# openmv4.net
KiCad netlist of a schematic drawn in Altium Designer
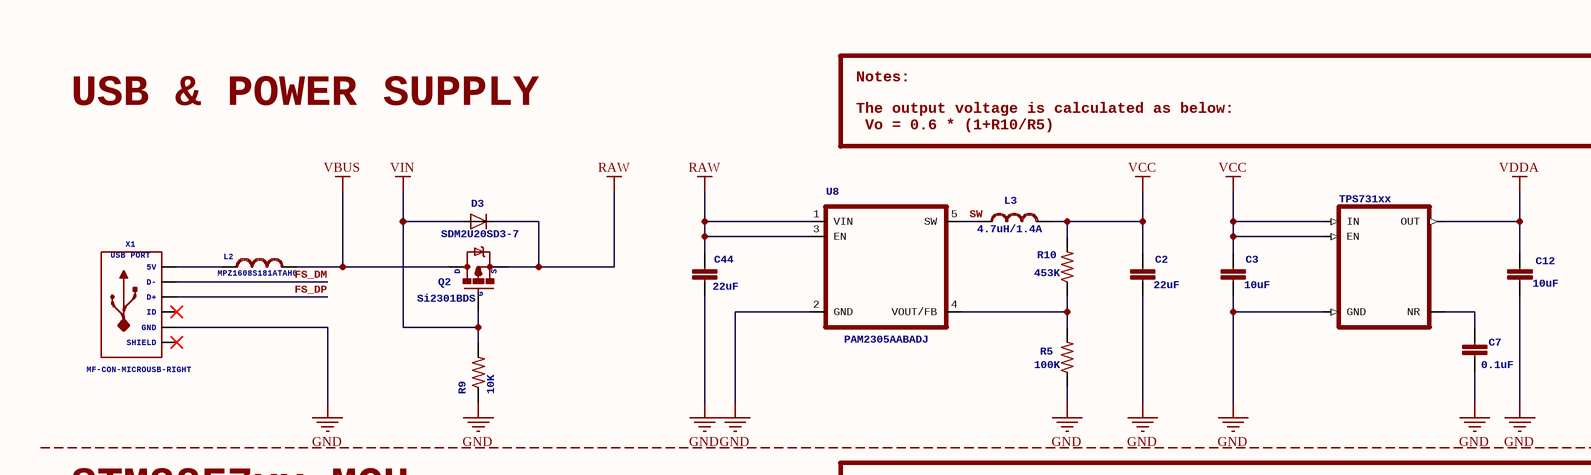
[diagram p0: openmv4.SchDoc, top left]
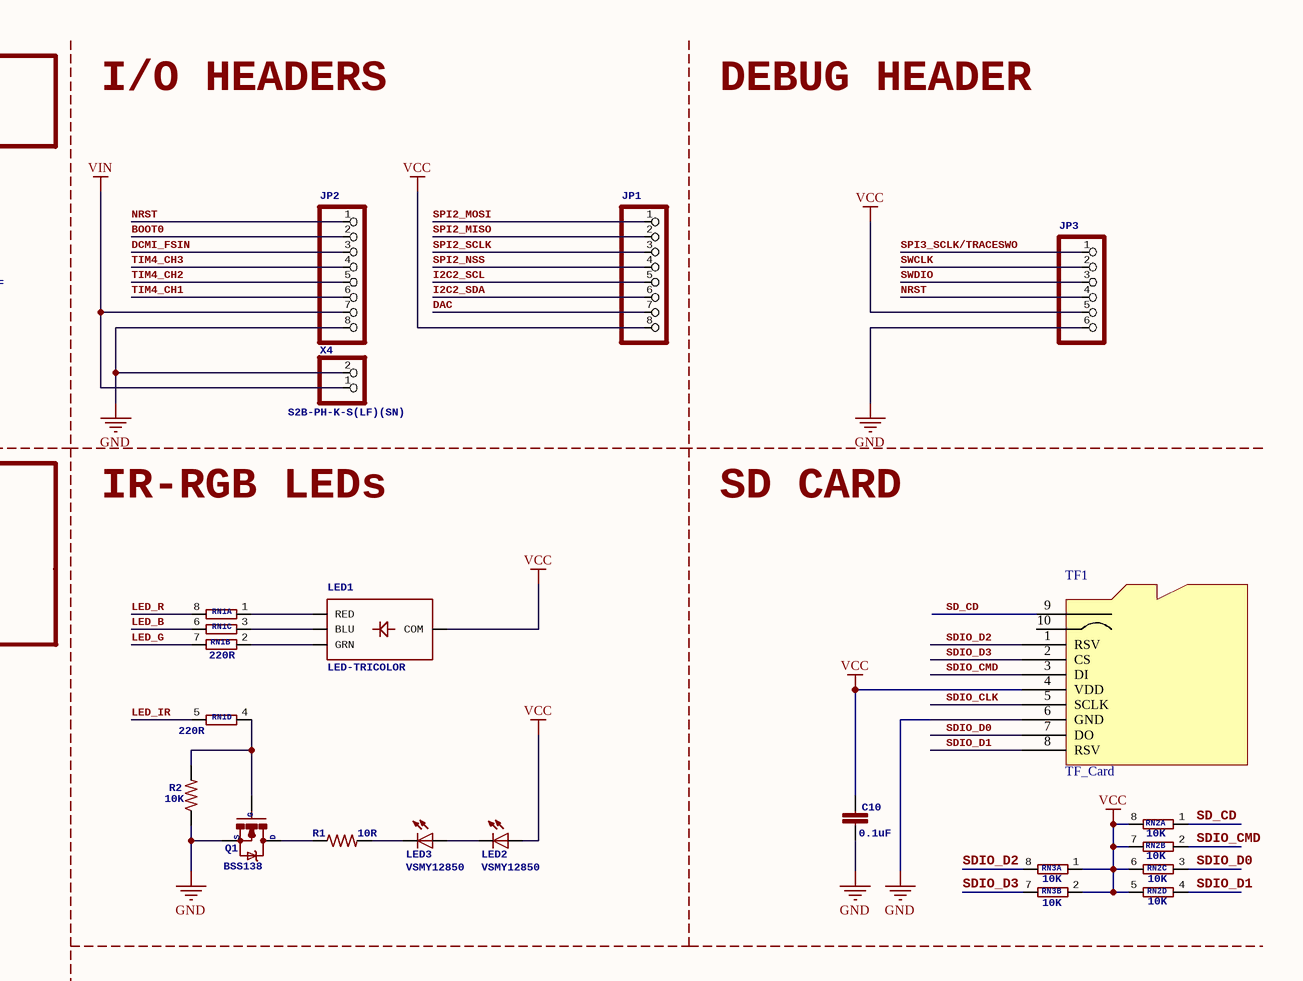
[diagram p1: openmv4.SchDoc, top right]
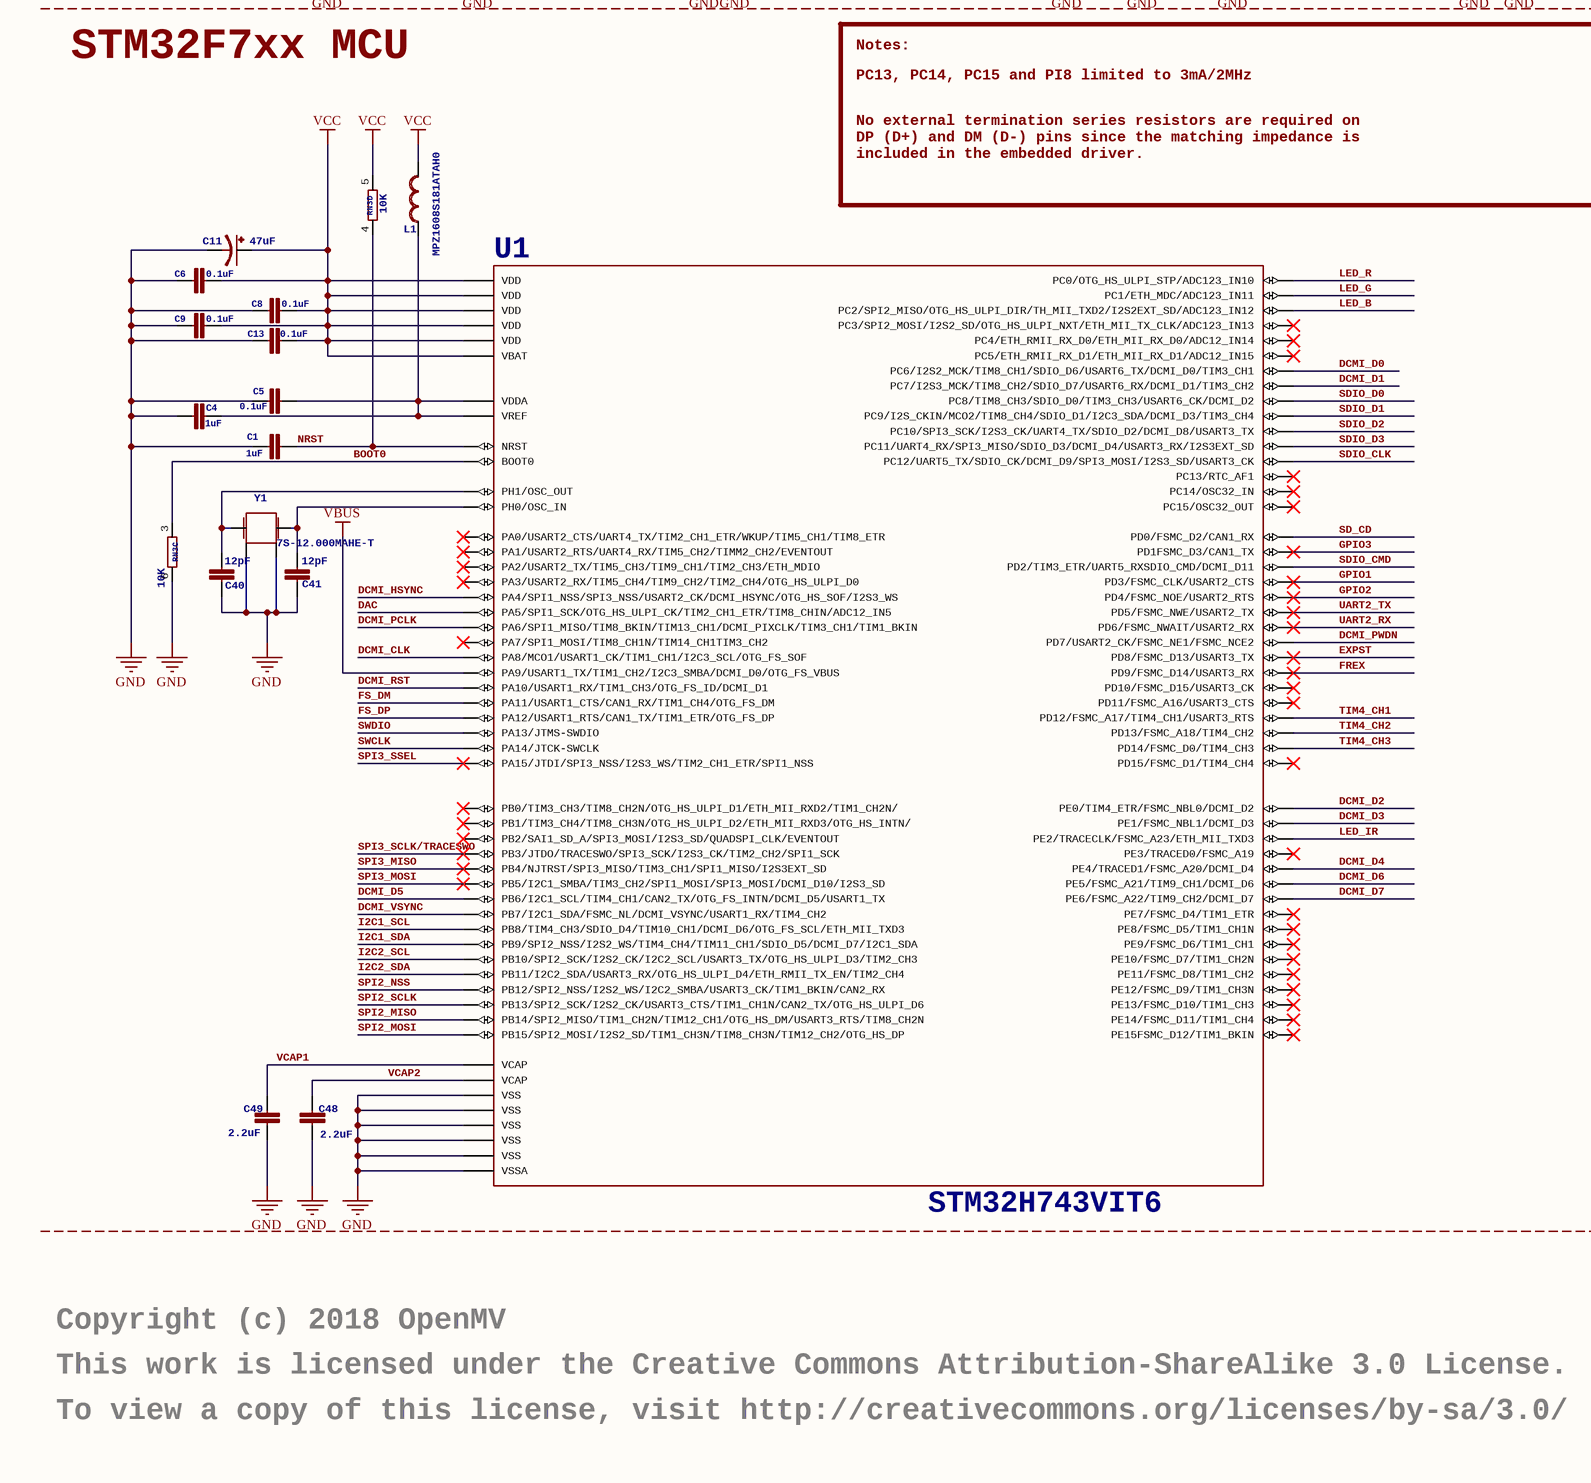
[diagram p2: openmv4.SchDoc, bottom left]
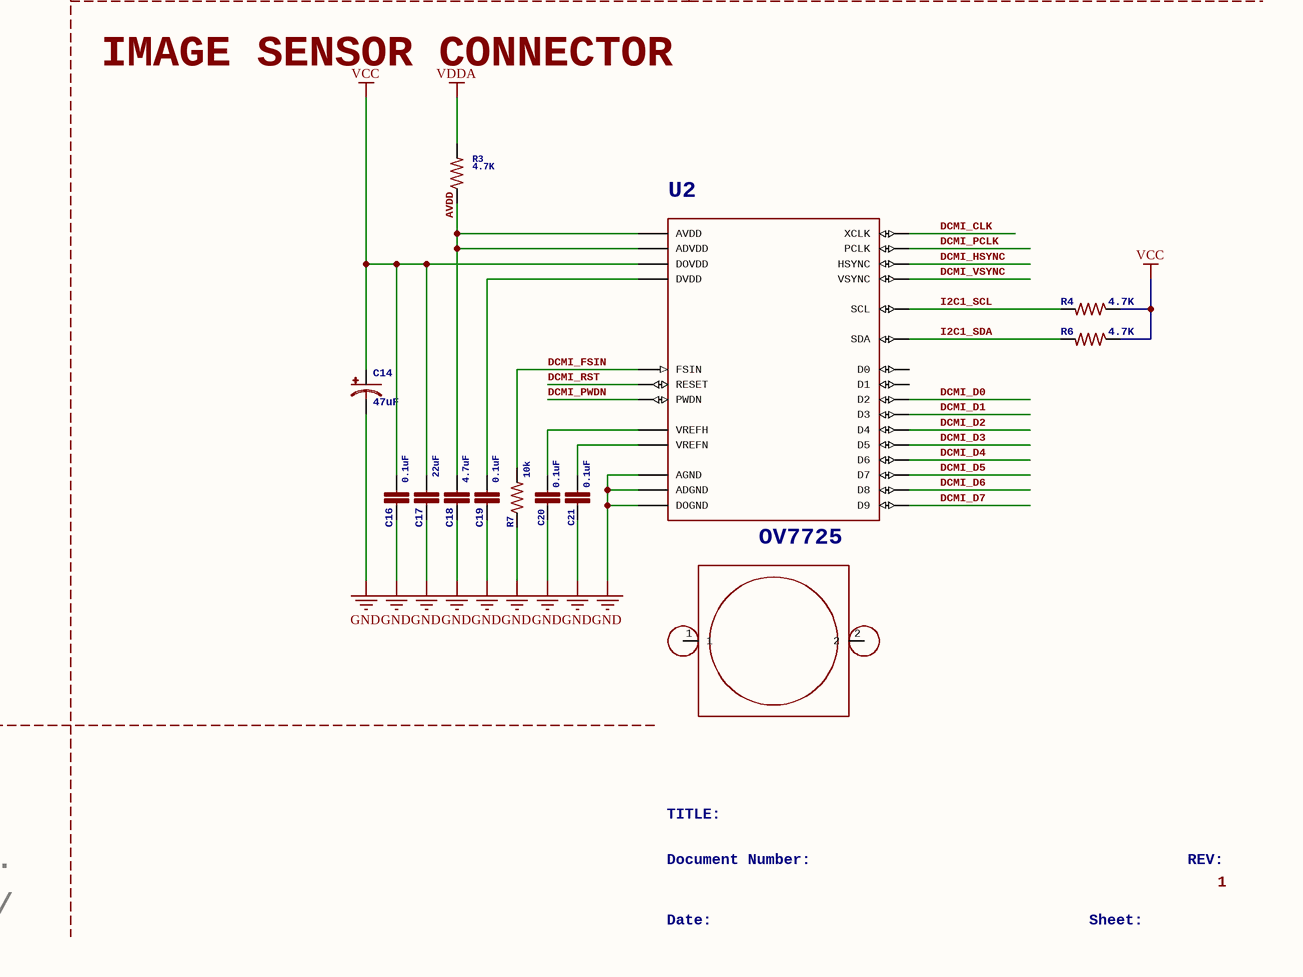
[diagram p3: openmv4.SchDoc, bottom right]

(export (version "E")
  (design (tool "Eeschema 10.0.6"))
  (components
    (comp (ref "C1")
      (value "1uF")
      (footprint "C0603")
      (description "CapacitorStandard 0603 ceramic capacitor, and 0.1\" leaded capacitor.")
      (libsource (lib "sfe") (part "CAP0603-CAP"))
    )
    (comp (ref "C2")
      (value "22uF")
      (footprint "C0805")
      (description "CapacitorStandard 0603 ceramic capacitor, and 0.1\" leaded capacitor.")
      (libsource (lib "") (part "CAP0805_1"))
    )
    (comp (ref "C3")
      (value "10uF")
      (footprint "C0805")
      (description "CapacitorStandard 0603 ceramic capacitor, and 0.1\" leaded capacitor.")
      (libsource (lib "") (part "CAP0805_1"))
    )
    (comp (ref "C4")
      (value "1uF")
      (footprint "C0603")
      (description "CapacitorStandard 0603 ceramic capacitor, and 0.1\" leaded capacitor.")
      (libsource (lib "sfe") (part "CAP0603-CAP"))
    )
    (comp (ref "C5")
      (value "0.1uF")
      (footprint "C0603")
      (description "CapacitorStandard 0603 ceramic capacitor, and 0.1\" leaded capacitor.")
      (libsource (lib "sfe") (part "CAP0603-CAP"))
    )
    (comp (ref "C6")
      (value "0.1uF")
      (footprint "C0603")
      (description "CapacitorStandard 0603 ceramic capacitor, and 0.1\" leaded capacitor.")
      (libsource (lib "sfe") (part "CAP0603-CAP"))
    )
    (comp (ref "C7")
      (value "0.1uF")
      (footprint "C0603")
      (description "CapacitorStandard 0603 ceramic capacitor, and 0.1\" leaded capacitor.")
      (libsource (lib "") (part "CAP0603-CAP_1"))
    )
    (comp (ref "C8")
      (value "0.1uF")
      (footprint "C0603")
      (description "CapacitorStandard 0603 ceramic capacitor, and 0.1\" leaded capacitor.")
      (libsource (lib "sfe") (part "CAP0603-CAP"))
    )
    (comp (ref "C9")
      (value "0.1uF")
      (footprint "C0603")
      (description "CapacitorStandard 0603 ceramic capacitor, and 0.1\" leaded capacitor.")
      (libsource (lib "sfe") (part "CAP0603-CAP"))
    )
    (comp (ref "C10")
      (value "0.1uF")
      (footprint "C0603")
      (description "CapacitorStandard 0603 ceramic capacitor, and 0.1\" leaded capacitor.")
      (libsource (lib "") (part "CAP0603-CAP_1"))
    )
    (comp (ref "C11") (value "47uF") (footprint "EIA3216") (libsource (lib "sfe") (part "CAP_POL1206")))
    (comp (ref "C12")
      (value "10uF")
      (footprint "C0805")
      (description "CapacitorStandard 0603 ceramic capacitor, and 0.1\" leaded capacitor.")
      (libsource (lib "") (part "CAP0805_1"))
    )
    (comp (ref "C13")
      (value "0.1uF")
      (footprint "C0603")
      (description "CapacitorStandard 0603 ceramic capacitor, and 0.1\" leaded capacitor.")
      (libsource (lib "sfe") (part "CAP0603-CAP"))
    )
    (comp (ref "C14") (value "47uF") (footprint "EIA3216") (libsource (lib "") (part "CAP_POL1206_1")))
    (comp (ref "C16")
      (value "0.1uF")
      (footprint "C0603")
      (description "CapacitorStandard 0603 ceramic capacitor, and 0.1\" leaded capacitor.")
      (libsource (lib "sfe") (part "CAP0603-CAP"))
    )
    (comp (ref "C17")
      (value "22uF")
      (footprint "C0805")
      (description "CapacitorStandard 0603 ceramic capacitor, and 0.1\" leaded capacitor.")
      (libsource (lib "sfe") (part "CAP0805"))
    )
    (comp (ref "C18")
      (value "4.7uF")
      (footprint "C0603")
      (description "CapacitorStandard 0603 ceramic capacitor, and 0.1\" leaded capacitor.")
      (libsource (lib "sfe") (part "CAP0603-CAP"))
    )
    (comp (ref "C19")
      (value "0.1uF")
      (footprint "C0603")
      (description "CapacitorStandard 0603 ceramic capacitor, and 0.1\" leaded capacitor.")
      (libsource (lib "sfe") (part "CAP0603-CAP"))
    )
    (comp (ref "C20")
      (value "0.1uF")
      (footprint "C0603")
      (description "CapacitorStandard 0603 ceramic capacitor, and 0.1\" leaded capacitor.")
      (libsource (lib "") (part "CAP0603-CAP_1"))
    )
    (comp (ref "C21")
      (value "0.1uF")
      (footprint "C0603")
      (description "CapacitorStandard 0603 ceramic capacitor, and 0.1\" leaded capacitor.")
      (libsource (lib "") (part "CAP0603-CAP_1"))
    )
    (comp (ref "C40")
      (value "12pF")
      (footprint "C0603")
      (description "CapacitorStandard 0603 ceramic capacitor, and 0.1\" leaded capacitor.")
      (libsource (lib "") (part "CAP0603-CAP_2"))
    )
    (comp (ref "C41")
      (value "12pF")
      (footprint "C0603")
      (description "CapacitorStandard 0603 ceramic capacitor, and 0.1\" leaded capacitor.")
      (libsource (lib "") (part "CAP0603-CAP_2"))
    )
    (comp (ref "C44")
      (value "22uF")
      (footprint "C0805")
      (description "CapacitorStandard 0603 ceramic capacitor, and 0.1\" leaded capacitor.")
      (libsource (lib "") (part "CAP0805_1"))
    )
    (comp (ref "C48")
      (value "2.2uF")
      (footprint "C0603")
      (description "CapacitorStandard 0603 ceramic capacitor, and 0.1\" leaded capacitor.")
      (libsource (lib "") (part "CAP0603-CAP_1"))
    )
    (comp (ref "C49")
      (value "2.2uF")
      (footprint "C0603")
      (description "CapacitorStandard 0603 ceramic capacitor, and 0.1\" leaded capacitor.")
      (libsource (lib "") (part "CAP0603-CAP_1"))
    )
    (comp (ref "D3") (value "SDM2U20SD3-7") (footprint "SOD323") (libsource (lib "sfe") (part "DIODESOD")))
    (comp (ref "JP1")
      (value "PINHD-1X8")
      (footprint "1X08")
      (description "PIN HEADER")
      (libsource (lib "pinhead") (part "PINHD-1X8"))
    )
    (comp (ref "JP2")
      (value "PINHD-1X8")
      (footprint "1X08")
      (description "PIN HEADER")
      (libsource (lib "pinhead") (part "PINHD-1X8"))
    )
    (comp (ref "JP3")
      (value "PINHD-1X6")
      (footprint "1X06")
      (description "PIN HEADER")
      (libsource (lib "pinhead") (part "PINHD-1X6"))
    )
    (comp (ref "L1")
      (value "MPZ1608S181ATAH0")
      (footprint "l0603")
      (libsource (lib "sfe") (part "INDUCTOR0603"))
    )
    (comp (ref "L2")
      (value "MPZ1608S181ATAH0")
      (footprint "l0603")
      (libsource (lib "sfe") (part "INDUCTOR0603"))
    )
    (comp (ref "L3") (value "4.7uH/1.4A") (footprint "1007") (libsource (lib "sfe") (part "INDUCTOR1007")))
    (comp (ref "LED1")
      (value "LED-TRICOLOR")
      (footprint "LED-TRICOLOR-SMD-MF")
      (libsource (lib "sfe") (part "LED-TRICOLOR"))
    )
    (comp (ref "LED2") (value "VSMY12850") (footprint "LED-1206") (libsource (lib "sfe") (part "LED1206")))
    (comp (ref "LED3") (value "VSMY12850") (footprint "LED-1206") (libsource (lib "sfe") (part "LED1206")))
    (comp (ref "LM1")
      (value "LENSMOUNT20MM")
      (footprint "LENSMOUNT-20MM")
      (libsource (lib "omnivision") (part "LENSMOUNT20MM"))
    )
    (comp (ref "Q1")
      (value "BSS138")
      (footprint "SOT23-3")
      (fields (field (name "D") "D") (field (name "S") "S") (field (name "G") "G"))
      (libsource (lib "sfe") (part "MOSFET-NCHANNELSMD"))
    )
    (comp (ref "Q2")
      (value "Si2301BDS")
      (footprint "SOT23-3")
      (fields (field (name "D") "D") (field (name "S") "S") (field (name "G") "G"))
      (libsource (lib "sfe") (part "MOSFET-PCHANNELSMD"))
    )
    (comp (ref "R1")
      (value "10R")
      (footprint "R0603")
      (description "ResistorBasic schematic elements and footprints for 0603, 1206, and PTH resistors.")
      (libsource (lib "sfe") (part "RESISTOR0603-RES"))
    )
    (comp (ref "R2")
      (value "10K")
      (footprint "R0603")
      (description "ResistorBasic schematic elements and footprints for 0603, 1206, and PTH resistors.")
      (libsource (lib "sfe") (part "RESISTOR0603-RES"))
    )
    (comp (ref "R3")
      (value "4.7K")
      (footprint "R0603")
      (description "ResistorBasic schematic elements and footprints for 0603, 1206, and PTH resistors.")
      (libsource (lib "sfe") (part "RESISTOR0603-RES"))
    )
    (comp (ref "R4")
      (value "4.7K")
      (footprint "R0603")
      (description "ResistorBasic schematic elements and footprints for 0603, 1206, and PTH resistors.")
      (libsource (lib "sfe") (part "RESISTOR0603-RES"))
    )
    (comp (ref "R5")
      (value "100K")
      (footprint "R0603")
      (description "ResistorBasic schematic elements and footprints for 0603, 1206, and PTH resistors.")
      (libsource (lib "sfe") (part "RESISTOR0603-RES"))
    )
    (comp (ref "R6")
      (value "4.7K")
      (footprint "R0603")
      (description "ResistorBasic schematic elements and footprints for 0603, 1206, and PTH resistors.")
      (libsource (lib "sfe") (part "RESISTOR0603-RES"))
    )
    (comp (ref "R7")
      (value "10k")
      (footprint "R0603")
      (description "ResistorBasic schematic elements and footprints for 0603, 1206, and PTH resistors.")
      (libsource (lib "sfe") (part "RESISTOR0603-RES"))
    )
    (comp (ref "R9")
      (value "10K")
      (footprint "R0603")
      (description "ResistorBasic schematic elements and footprints for 0603, 1206, and PTH resistors.")
      (libsource (lib "sfe") (part "RESISTOR0603-RES"))
    )
    (comp (ref "R10")
      (value "453K")
      (footprint "R0603")
      (description "ResistorBasic schematic elements and footprints for 0603, 1206, and PTH resistors.")
      (libsource (lib "sfe") (part "RESISTOR0603-RES"))
    )
    (comp (ref "RN1")
      (value "220R")
      (footprint "EXBV8V")
      (description "Array Chip Resistor   Source: RS Component / Phycomp")
      (libsource (lib "resistor-dil") (part "4R-NEXBV8V"))
    )
    (comp (ref "RN2")
      (value "10K")
      (footprint "EXBV8V")
      (description "Array Chip Resistor   Source: RS Component / Phycomp")
      (libsource (lib "resistor-dil") (part "4R-NEXBV8V"))
    )
    (comp (ref "RN3")
      (value "10K")
      (footprint "EXBV8V")
      (description "Array Chip Resistor   Source: RS Component / Phycomp")
      (libsource (lib "resistor-dil") (part "4R-NEXBV8V"))
    )
    (comp (ref "TF1")
      (value "TF_Card")
      (footprint "TF-2")
      (libsource (lib "Desiger_Schlib") (part "TF_CADE"))
    )
    (comp (ref "U1")
      (value "STM32H743VIT6")
      (footprint "LQFP100")
      (libsource (lib "stm32") (part "STM32F746LQFP100"))
    )
    (comp (ref "U2") (value "OV7725") (footprint "CSP2-28") (libsource (lib "omnivision") (part "OV7725")))
    (comp (ref "U5")
      (value "TPS731XX")
      (footprint "SOT23-5")
      (fields (field (name "TPS731XX") "TPS731xx"))
      (libsource (lib "mux") (part "TPS731XX"))
    )
    (comp (ref "U8")
      (value "PAM2305AABADJ")
      (footprint "SOT23-5")
      (libsource (lib "regulators") (part "PAM2305AAB330"))
    )
    (comp (ref "X1")
      (value "MF-CON-MICROUSB-RIGHT")
      (footprint "MICROUSB-RIGHT")
      (fields
        (field (name "USBPORT") "USB PORT")
        (field (name "5V") "5V")
        (field (name "D-") "D-")
        (field (name "D+") "D+")
        (field (name "ID") "ID")
        (field (name "GND") "GND")
        (field (name "SHIELD") "SHIELD")
      )
      (libsource (lib "MF_Connectors") (part "USB_MICRO_RIGHT"))
    )
    (comp (ref "X4")
      (value "S2B-PH-K-S(LF)(SN)")
      (footprint "JST-PH-2-THM-RA")
      (libsource (lib "adafruit-updated") (part "JST_2PIN-THM-RA"))
    )
    (comp (ref "Y1")
      (value "7S-12.000MAHE-T")
      (footprint "XTAL-SMD-3225_4P")
      (description "CrystalsVarious standard crystals. Proven footprints. Spark Fun Electronics SKU : COM-00534")
      (libsource (lib "mux") (part "CRYSTAL2.5X2.0"))
    )
  )
  (nets
    (net (code "1") (name "/AVDD") (class "Default")
      (node (ref "C18") (pin "1") (pinfunction "1_1") (pintype "passive"))
      (node (ref "R3") (pin "1") (pinfunction "1_1") (pintype "passive"))
      (node (ref "U2") (pin "A1") (pinfunction "ADVDD_A1") (pintype "power_in"))
      (node (ref "U2") (pin "B3") (pinfunction "AVDD_B3") (pintype "power_in"))
    )
    (net (code "2") (name "/BOOT0") (class "Default")
      (node (ref "JP2") (pin "2") (pinfunction "2_2") (pintype "passive"))
      (node (ref "RN3") (pin "3") (pinfunction "1_3") (pintype "passive"))
      (node (ref "U1") (pin "94") (pinfunction "BOOT0_94") (pintype "bidirectional"))
    )
    (net (code "3") (name "/DAC") (class "Default")
      (node (ref "JP1") (pin "7") (pinfunction "7_7") (pintype "passive"))
      (node (ref "U1") (pin "29") (pinfunction "PA5/SPI1_SCK/OTG_HS_ULPI_CK/TIM2_CH1_ETR/TIM8_CHIN/ADC12_IN5_29") (pintype "bidirectional"))
    )
    (net (code "4") (name "/DCMI_CLK") (class "Default")
      (node (ref "U1") (pin "67") (pinfunction "PA8/MCO1/USART1_CK/TIM1_CH1/I2C3_SCL/OTG_FS_SOF_67") (pintype "bidirectional"))
      (node (ref "U2") (pin "F3") (pinfunction "XCLK_F3") (pintype "bidirectional"))
    )
    (net (code "5") (name "/DCMI_D0") (class "Default")
      (node (ref "U1") (pin "63") (pinfunction "PC6/I2S2_MCK/TIM8_CH1/SDIO_D6/USART6_TX/DCMI_D0/TIM3_CH1_63") (pintype "bidirectional"))
      (node (ref "U2") (pin "F5") (pinfunction "D2_F5") (pintype "bidirectional"))
    )
    (net (code "6") (name "/DCMI_D1") (class "Default")
      (node (ref "U1") (pin "64") (pinfunction "PC7/I2S3_MCK/TIM8_CH2/SDIO_D7/USART6_RX/DCMI_D1/TIM3_CH2_64") (pintype "bidirectional"))
      (node (ref "U2") (pin "F2") (pinfunction "D3_F2") (pintype "bidirectional"))
    )
    (net (code "7") (name "/DCMI_D2") (class "Default")
      (node (ref "U1") (pin "97") (pinfunction "PE0/TIM4_ETR/FSMC_NBL0/DCMI_D2_97") (pintype "bidirectional"))
      (node (ref "U2") (pin "D6") (pinfunction "D4_D6") (pintype "bidirectional"))
    )
    (net (code "8") (name "/DCMI_D3") (class "Default")
      (node (ref "U1") (pin "98") (pinfunction "PE1/FSMC_NBL1/DCMI_D3_98") (pintype "bidirectional"))
      (node (ref "U2") (pin "D1") (pinfunction "D5_D1") (pintype "bidirectional"))
    )
    (net (code "9") (name "/DCMI_D4") (class "Default")
      (node (ref "U1") (pin "3") (pinfunction "PE4/TRACED1/FSMC_A20/DCMI_D4_3") (pintype "bidirectional"))
      (node (ref "U2") (pin "E6") (pinfunction "D6_E6") (pintype "bidirectional"))
    )
    (net (code "10") (name "/DCMI_D5") (class "Default")
      (node (ref "U1") (pin "92") (pinfunction "PB6/I2C1_SCL/TIM4_CH1/CAN2_TX/OTG_FS_INTN/DCMI_D5/USART1_TX_92") (pintype "bidirectional"))
      (node (ref "U2") (pin "E1") (pinfunction "D7_E1") (pintype "bidirectional"))
    )
    (net (code "11") (name "/DCMI_D6") (class "Default")
      (node (ref "U1") (pin "4") (pinfunction "PE5/FSMC_A21/TIM9_CH1/DCMI_D6_4") (pintype "bidirectional"))
      (node (ref "U2") (pin "F6") (pinfunction "D8_F6") (pintype "bidirectional"))
    )
    (net (code "12") (name "/DCMI_D7") (class "Default")
      (node (ref "U1") (pin "5") (pinfunction "PE6/FSMC_A22/TIM9_CH2/DCMI_D7_5") (pintype "bidirectional"))
      (node (ref "U2") (pin "F1") (pinfunction "D9_F1") (pintype "bidirectional"))
    )
    (net (code "13") (name "/DCMI_FSIN") (class "Default")
      (node (ref "JP2") (pin "3") (pinfunction "3_3") (pintype "passive"))
      (node (ref "R7") (pin "2") (pinfunction "2_2") (pintype "passive"))
      (node (ref "U2") (pin "A4") (pinfunction "FSIN_A4") (pintype "input"))
    )
    (net (code "14") (name "/DCMI_HSYNC") (class "Default")
      (node (ref "U1") (pin "28") (pinfunction "PA4/SPI1_NSS/SPI3_NSS/USART2_CK/DCMI_HSYNC/OTG_HS_SOF/I2S3_WS_28") (pintype "bidirectional"))
      (node (ref "U2") (pin "B6") (pinfunction "HSYNC_B6") (pintype "bidirectional"))
    )
    (net (code "15") (name "/DCMI_PCLK") (class "Default")
      (node (ref "U1") (pin "30") (pinfunction "PA6/SPI1_MISO/TIM8_BKIN/TIM13_CH1/DCMI_PIXCLK/TIM3_CH1/TIM1_BKIN_30") (pintype "bidirectional"))
      (node (ref "U2") (pin "E4") (pinfunction "PCLK_E4") (pintype "bidirectional"))
    )
    (net (code "16") (name "/DCMI_PWDN") (class "Default")
      (node (ref "U1") (pin "88") (pinfunction "PD7/USART2_CK/FSMC_NE1/FSMC_NCE2_88") (pintype "bidirectional"))
      (node (ref "U2") (pin "C1") (pinfunction "PWDN_C1") (pintype "bidirectional"))
    )
    (net (code "17") (name "/DCMI_RST") (class "Default")
      (node (ref "U1") (pin "69") (pinfunction "PA10/USART1_RX/TIM1_CH3/OTG_FS_ID/DCMI_D1_69") (pintype "bidirectional"))
      (node (ref "U2") (pin "A2") (pinfunction "RESET_A2") (pintype "bidirectional"))
    )
    (net (code "18") (name "/DCMI_VSYNC") (class "Default")
      (node (ref "U1") (pin "93") (pinfunction "PB7/I2C1_SDA/FSMC_NL/DCMI_VSYNC/USART1_RX/TIM4_CH2_93") (pintype "bidirectional"))
      (node (ref "U2") (pin "C6") (pinfunction "VSYNC_C6") (pintype "bidirectional"))
    )
    (net (code "19") (name "/EXPST") (class "Default")
      (node (ref "U1") (pin "55") (pinfunction "PD8/FSMC_D13/USART3_TX_55") (pintype "bidirectional+no_connect"))
    )
    (net (code "20") (name "/FREX") (class "Default")
      (node (ref "U1") (pin "56") (pinfunction "PD9/FSMC_D14/USART3_RX_56") (pintype "bidirectional+no_connect"))
    )
    (net (code "21") (name "/FS_DM") (class "Default")
      (node (ref "U1") (pin "70") (pinfunction "PA11/USART1_CTS/CAN1_RX/TIM1_CH4/OTG_FS_DM_70") (pintype "bidirectional"))
      (node (ref "X1") (pin "2") (pinfunction "D-_2") (pintype "bidirectional"))
    )
    (net (code "22") (name "/FS_DP") (class "Default")
      (node (ref "U1") (pin "71") (pinfunction "PA12/USART1_RTS/CAN1_TX/TIM1_ETR/OTG_FS_DP_71") (pintype "bidirectional"))
      (node (ref "X1") (pin "3") (pinfunction "D+_3") (pintype "bidirectional"))
    )
    (net (code "23") (name "/GPIO1") (class "Default")
      (node (ref "U1") (pin "84") (pinfunction "PD3/FSMC_CLK/USART2_CTS_84") (pintype "bidirectional+no_connect"))
    )
    (net (code "24") (name "/GPIO2") (class "Default")
      (node (ref "U1") (pin "85") (pinfunction "PD4/FSMC_NOE/USART2_RTS_85") (pintype "bidirectional+no_connect"))
    )
    (net (code "25") (name "/GPIO3") (class "Default")
      (node (ref "U1") (pin "82") (pinfunction "PD1FSMC_D3/CAN1_TX_82") (pintype "bidirectional+no_connect"))
    )
    (net (code "26") (name "/I2C1_SCL") (class "Default")
      (node (ref "R4") (pin "2") (pinfunction "2_2") (pintype "passive"))
      (node (ref "U1") (pin "95") (pinfunction "PB8/TIM4_CH3/SDIO_D4/TIM10_CH1/DCMI_D6/OTG_FS_SCL/ETH_MII_TXD3_95") (pintype "bidirectional"))
      (node (ref "U2") (pin "A5") (pinfunction "SCL_A5") (pintype "bidirectional"))
    )
    (net (code "27") (name "/I2C1_SDA") (class "Default")
      (node (ref "R6") (pin "2") (pinfunction "2_2") (pintype "passive"))
      (node (ref "U1") (pin "96") (pinfunction "PB9/SPI2_NSS/I2S2_WS/TIM4_CH4/TIM11_CH1/SDIO_D5/DCMI_D7/I2C1_SDA_96") (pintype "bidirectional"))
      (node (ref "U2") (pin "B5") (pinfunction "SDA_B5") (pintype "bidirectional"))
    )
    (net (code "28") (name "/I2C2_SCL") (class "Default")
      (node (ref "JP1") (pin "5") (pinfunction "5_5") (pintype "passive"))
      (node (ref "U1") (pin "46") (pinfunction "PB10/SPI2_SCK/I2S2_CK/I2C2_SCL/USART3_TX/OTG_HS_ULPI_D3/TIM2_CH3_46") (pintype "bidirectional"))
    )
    (net (code "29") (name "/I2C2_SDA") (class "Default")
      (node (ref "JP1") (pin "6") (pinfunction "6_6") (pintype "passive"))
      (node (ref "U1") (pin "47") (pinfunction "PB11/I2C2_SDA/USART3_RX/OTG_HS_ULPI_D4/ETH_RMII_TX_EN/TIM2_CH4_47") (pintype "bidirectional"))
    )
    (net (code "30") (name "/LED_B") (class "Default")
      (node (ref "RN1") (pin "6") (pinfunction "2_6") (pintype "passive"))
      (node (ref "U1") (pin "17") (pinfunction "PC2/SPI2_MISO/OTG_HS_ULPI_DIR/TH_MII_TXD2/I2S2EXT_SD/ADC123_IN12_17") (pintype "bidirectional"))
    )
    (net (code "31") (name "/LED_G") (class "Default")
      (node (ref "RN1") (pin "7") (pinfunction "2_7") (pintype "passive"))
      (node (ref "U1") (pin "16") (pinfunction "PC1/ETH_MDC/ADC123_IN11_16") (pintype "bidirectional"))
    )
    (net (code "32") (name "/LED_IR") (class "Default")
      (node (ref "RN1") (pin "5") (pinfunction "2_5") (pintype "passive"))
      (node (ref "U1") (pin "1") (pinfunction "PE2/TRACECLK/FSMC_A23/ETH_MII_TXD3_1") (pintype "bidirectional"))
    )
    (net (code "33") (name "/LED_R") (class "Default")
      (node (ref "RN1") (pin "8") (pinfunction "2_8") (pintype "passive"))
      (node (ref "U1") (pin "15") (pinfunction "PC0/OTG_HS_ULPI_STP/ADC123_IN10_15") (pintype "bidirectional"))
    )
    (net (code "34") (name "/NRST") (class "Default")
      (node (ref "C1") (pin "1") (pinfunction "1_1") (pintype "passive"))
      (node (ref "JP2") (pin "1") (pinfunction "1_1") (pintype "passive"))
      (node (ref "JP3") (pin "4") (pinfunction "4_4") (pintype "passive"))
      (node (ref "RN3") (pin "4") (pinfunction "1_4") (pintype "passive"))
      (node (ref "U1") (pin "14") (pinfunction "NRST_14") (pintype "bidirectional"))
    )
    (net (code "35") (name "/SDIO_CLK") (class "Default")
      (node (ref "TF1") (pin "5") (pinfunction "SCLK_5") (pintype "passive"))
      (node (ref "U1") (pin "80") (pinfunction "PC12/UART5_TX/SDIO_CK/DCMI_D9/SPI3_MOSI/I2S3_SD/USART3_CK_80") (pintype "bidirectional"))
    )
    (net (code "36") (name "/SDIO_CMD") (class "Default")
      (node (ref "RN2") (pin "2") (pinfunction "1_2") (pintype "passive"))
      (node (ref "TF1") (pin "3") (pinfunction "DI_3") (pintype "passive"))
      (node (ref "U1") (pin "83") (pinfunction "PD2/TIM3_ETR/UART5_RXSDIO_CMD/DCMI_D11_83") (pintype "bidirectional"))
    )
    (net (code "37") (name "/SDIO_D0") (class "Default")
      (node (ref "RN2") (pin "3") (pinfunction "1_3") (pintype "passive"))
      (node (ref "TF1") (pin "7") (pinfunction "DO_7") (pintype "passive"))
      (node (ref "U1") (pin "65") (pinfunction "PC8/TIM8_CH3/SDIO_D0/TIM3_CH3/USART6_CK/DCMI_D2_65") (pintype "bidirectional"))
    )
    (net (code "38") (name "/SDIO_D1") (class "Default")
      (node (ref "RN2") (pin "4") (pinfunction "1_4") (pintype "passive"))
      (node (ref "TF1") (pin "8") (pinfunction "RSV_8") (pintype "passive"))
      (node (ref "U1") (pin "66") (pinfunction "PC9/I2S_CKIN/MCO2/TIM8_CH4/SDIO_D1/I2C3_SDA/DCMI_D3/TIM3_CH4_66") (pintype "bidirectional"))
    )
    (net (code "39") (name "/SDIO_D2") (class "Default")
      (node (ref "RN3") (pin "8") (pinfunction "2_8") (pintype "passive"))
      (node (ref "TF1") (pin "1") (pinfunction "RSV_1") (pintype "passive"))
      (node (ref "U1") (pin "78") (pinfunction "PC10/SPI3_SCK/I2S3_CK/UART4_TX/SDIO_D2/DCMI_D8/USART3_TX_78") (pintype "bidirectional"))
    )
    (net (code "40") (name "/SDIO_D3") (class "Default")
      (node (ref "RN3") (pin "7") (pinfunction "2_7") (pintype "passive"))
      (node (ref "TF1") (pin "2") (pinfunction "CS_2") (pintype "passive"))
      (node (ref "U1") (pin "79") (pinfunction "PC11/UART4_RX/SPI3_MISO/SDIO_D3/DCMI_D4/USART3_RX/I2S3EXT_SD_79") (pintype "bidirectional"))
    )
    (net (code "41") (name "/SD_CD") (class "Default")
      (node (ref "RN2") (pin "1") (pinfunction "1_1") (pintype "passive"))
      (node (ref "TF1") (pin "9") (pintype "passive"))
      (node (ref "U1") (pin "81") (pinfunction "PD0/FSMC_D2/CAN1_RX_81") (pintype "bidirectional"))
    )
    (net (code "42") (name "/SPI2_MISO") (class "Default")
      (node (ref "JP1") (pin "2") (pinfunction "2_2") (pintype "passive"))
      (node (ref "U1") (pin "53") (pinfunction "PB14/SPI2_MISO/TIM1_CH2N/TIM12_CH1/OTG_HS_DM/USART3_RTS/TIM8_CH2N_53") (pintype "bidirectional"))
    )
    (net (code "43") (name "/SPI2_MOSI") (class "Default")
      (node (ref "JP1") (pin "1") (pinfunction "1_1") (pintype "passive"))
      (node (ref "U1") (pin "54") (pinfunction "PB15/SPI2_MOSI/I2S2_SD/TIM1_CH3N/TIM8_CH3N/TIM12_CH2/OTG_HS_DP_54") (pintype "bidirectional"))
    )
    (net (code "44") (name "/SPI2_NSS") (class "Default")
      (node (ref "JP1") (pin "4") (pinfunction "4_4") (pintype "passive"))
      (node (ref "U1") (pin "51") (pinfunction "PB12/SPI2_NSS/I2S2_WS/I2C2_SMBA/USART3_CK/TIM1_BKIN/CAN2_RX_51") (pintype "bidirectional"))
    )
    (net (code "45") (name "/SPI2_SCLK") (class "Default")
      (node (ref "JP1") (pin "3") (pinfunction "3_3") (pintype "passive"))
      (node (ref "U1") (pin "52") (pinfunction "PB13/SPI2_SCK/I2S2_CK/USART3_CTS/TIM1_CH1N/CAN2_TX/OTG_HS_ULPI_D6_52") (pintype "bidirectional"))
    )
    (net (code "46") (name "/SPI3_MISO") (class "Default")
      (node (ref "U1") (pin "90") (pinfunction "PB4/NJTRST/SPI3_MISO/TIM3_CH1/SPI1_MISO/I2S3EXT_SD_90") (pintype "bidirectional+no_connect"))
    )
    (net (code "47") (name "/SPI3_MOSI") (class "Default")
      (node (ref "U1") (pin "91") (pinfunction "PB5/I2C1_SMBA/TIM3_CH2/SPI1_MOSI/SPI3_MOSI/DCMI_D10/I2S3_SD_91") (pintype "bidirectional+no_connect"))
    )
    (net (code "48") (name "/SPI3_SCLK{slash}TRACESWO") (class "Default")
      (node (ref "JP3") (pin "1") (pinfunction "1_1") (pintype "passive"))
      (node (ref "U1") (pin "89") (pinfunction "PB3/JTDO/TRACESWO/SPI3_SCK/I2S3_CK/TIM2_CH2/SPI1_SCK_89") (pintype "bidirectional"))
    )
    (net (code "49") (name "/SPI3_SSEL") (class "Default")
      (node (ref "U1") (pin "77") (pinfunction "PA15/JTDI/SPI3_NSS/I2S3_WS/TIM2_CH1_ETR/SPI1_NSS_77") (pintype "bidirectional+no_connect"))
    )
    (net (code "50") (name "/SW") (class "Default")
      (node (ref "L3") (pin "1") (pinfunction "1_1") (pintype "passive"))
      (node (ref "U8") (pin "5") (pinfunction "SW_5") (pintype "power_in"))
    )
    (net (code "51") (name "/SWCLK") (class "Default")
      (node (ref "JP3") (pin "2") (pinfunction "2_2") (pintype "passive"))
      (node (ref "U1") (pin "76") (pinfunction "PA14/JTCK-SWCLK_76") (pintype "bidirectional"))
    )
    (net (code "52") (name "/SWDIO") (class "Default")
      (node (ref "JP3") (pin "3") (pinfunction "3_3") (pintype "passive"))
      (node (ref "U1") (pin "72") (pinfunction "PA13/JTMS-SWDIO_72") (pintype "bidirectional"))
    )
    (net (code "53") (name "/TIM4_CH1") (class "Default")
      (node (ref "JP2") (pin "6") (pinfunction "6_6") (pintype "passive"))
      (node (ref "U1") (pin "59") (pinfunction "PD12/FSMC_A17/TIM4_CH1/USART3_RTS_59") (pintype "bidirectional"))
    )
    (net (code "54") (name "/TIM4_CH2") (class "Default")
      (node (ref "JP2") (pin "5") (pinfunction "5_5") (pintype "passive"))
      (node (ref "U1") (pin "60") (pinfunction "PD13/FSMC_A18/TIM4_CH2_60") (pintype "bidirectional"))
    )
    (net (code "55") (name "/TIM4_CH3") (class "Default")
      (node (ref "JP2") (pin "4") (pinfunction "4_4") (pintype "passive"))
      (node (ref "U1") (pin "61") (pinfunction "PD14/FSMC_D0/TIM4_CH3_61") (pintype "bidirectional"))
    )
    (net (code "56") (name "/UART2_RX") (class "Default")
      (node (ref "U1") (pin "87") (pinfunction "PD6/FSMC_NWAIT/USART2_RX_87") (pintype "bidirectional+no_connect"))
    )
    (net (code "57") (name "/UART2_TX") (class "Default")
      (node (ref "U1") (pin "86") (pinfunction "PD5/FSMC_NWE/USART2_TX_86") (pintype "bidirectional+no_connect"))
    )
    (net (code "58") (name "/VCAP1") (class "Default")
      (node (ref "C49") (pin "1") (pinfunction "1_1") (pintype "passive"))
      (node (ref "U1") (pin "48") (pinfunction "VCAP_48") (pintype "power_in"))
    )
    (net (code "59") (name "/VCAP2") (class "Default")
      (node (ref "C48") (pin "1") (pinfunction "1_1") (pintype "passive"))
      (node (ref "U1") (pin "73") (pinfunction "VCAP_73") (pintype "power_in"))
    )
    (net (code "60") (name "GND") (class "Default")
      (node (ref "C1") (pin "2") (pinfunction "2_2") (pintype "passive"))
      (node (ref "C10") (pin "2") (pinfunction "2_2") (pintype "passive"))
      (node (ref "C11") (pin "C") (pinfunction "-_C") (pintype "passive"))
      (node (ref "C12") (pin "1") (pinfunction "1_1") (pintype "passive"))
      (node (ref "C13") (pin "2") (pinfunction "2_2") (pintype "passive"))
      (node (ref "C14") (pin "C") (pinfunction "-_C") (pintype "passive"))
      (node (ref "C16") (pin "2") (pinfunction "2_2") (pintype "passive"))
      (node (ref "C17") (pin "2") (pinfunction "2_2") (pintype "passive"))
      (node (ref "C18") (pin "2") (pinfunction "2_2") (pintype "passive"))
      (node (ref "C19") (pin "2") (pinfunction "2_2") (pintype "passive"))
      (node (ref "C2") (pin "1") (pinfunction "1_1") (pintype "passive"))
      (node (ref "C20") (pin "2") (pinfunction "2_2") (pintype "passive"))
      (node (ref "C21") (pin "2") (pinfunction "2_2") (pintype "passive"))
      (node (ref "C3") (pin "1") (pinfunction "1_1") (pintype "passive"))
      (node (ref "C4") (pin "2") (pinfunction "2_2") (pintype "passive"))
      (node (ref "C40") (pin "1") (pinfunction "1_1") (pintype "passive"))
      (node (ref "C41") (pin "1") (pinfunction "1_1") (pintype "passive"))
      (node (ref "C44") (pin "1") (pinfunction "1_1") (pintype "passive"))
      (node (ref "C48") (pin "2") (pinfunction "2_2") (pintype "passive"))
      (node (ref "C49") (pin "2") (pinfunction "2_2") (pintype "passive"))
      (node (ref "C5") (pin "2") (pinfunction "2_2") (pintype "passive"))
      (node (ref "C6") (pin "2") (pinfunction "2_2") (pintype "passive"))
      (node (ref "C7") (pin "2") (pinfunction "2_2") (pintype "passive"))
      (node (ref "C8") (pin "2") (pinfunction "2_2") (pintype "passive"))
      (node (ref "C9") (pin "2") (pinfunction "2_2") (pintype "passive"))
      (node (ref "JP2") (pin "8") (pinfunction "8_8") (pintype "passive"))
      (node (ref "JP3") (pin "6") (pinfunction "6_6") (pintype "passive"))
      (node (ref "Q1") (pin "2") (pinfunction "S_2") (pintype "passive"))
      (node (ref "R2") (pin "1") (pinfunction "1_1") (pintype "passive"))
      (node (ref "R5") (pin "1") (pinfunction "1_1") (pintype "passive"))
      (node (ref "R7") (pin "1") (pinfunction "1_1") (pintype "passive"))
      (node (ref "R9") (pin "1") (pinfunction "1_1") (pintype "passive"))
      (node (ref "RN3") (pin "6") (pinfunction "2_6") (pintype "passive"))
      (node (ref "TF1") (pin "6") (pinfunction "GND_6") (pintype "passive"))
      (node (ref "U1") (pin "10") (pinfunction "VSS_10") (pintype "power_in"))
      (node (ref "U1") (pin "19") (pinfunction "VSSA_19") (pintype "power_in"))
      (node (ref "U1") (pin "26") (pinfunction "VSS_26") (pintype "power_in"))
      (node (ref "U1") (pin "49") (pinfunction "VSS_49") (pintype "power_in"))
      (node (ref "U1") (pin "74") (pinfunction "VSS_74") (pintype "power_in"))
      (node (ref "U1") (pin "99") (pinfunction "VSS_99") (pintype "power_in"))
      (node (ref "U2") (pin "B1") (pinfunction "ADGND_B1") (pintype "power_in"))
      (node (ref "U2") (pin "B4") (pinfunction "AGND_B4") (pintype "power_in"))
      (node (ref "U2") (pin "F4") (pinfunction "DOGND_F4") (pintype "power_in"))
      (node (ref "U5") (pin "2") (pinfunction "GND_2") (pintype "input"))
      (node (ref "U8") (pin "2") (pinfunction "GND_2") (pintype "power_in"))
      (node (ref "X1") (pin "5") (pinfunction "GND_5") (pintype "power_in"))
      (node (ref "X4") (pin "2") (pinfunction "1_2") (pintype "passive"))
      (node (ref "Y1") (pin "2") (pinfunction "P$1_2") (pintype "power_in"))
      (node (ref "Y1") (pin "4") (pinfunction "P$2_4") (pintype "power_in"))
    )
    (net (code "61") (name "Net-(LED1-BLU)") (class "Default")
      (node (ref "LED1") (pin "3") (pinfunction "BLU_3") (pintype "bidirectional"))
      (node (ref "RN1") (pin "3") (pinfunction "1_3") (pintype "passive"))
    )
    (net (code "62") (name "Net-(LED1-GRN)") (class "Default")
      (node (ref "LED1") (pin "4") (pinfunction "GRN_4") (pintype "bidirectional"))
      (node (ref "RN1") (pin "2") (pinfunction "1_2") (pintype "passive"))
    )
    (net (code "63") (name "Net-(LED1-RED)") (class "Default")
      (node (ref "LED1") (pin "1") (pinfunction "RED_1") (pintype "bidirectional"))
      (node (ref "RN1") (pin "1") (pinfunction "1_1") (pintype "passive"))
    )
    (net (code "64") (name "Net-(LED2-Pad2)") (class "Default")
      (node (ref "LED2") (pin "2") (pinfunction "2_2") (pintype "passive"))
      (node (ref "LED3") (pin "1") (pinfunction "1_1") (pintype "passive"))
    )
    (net (code "65") (name "Net-(LED3-Pad2)") (class "Default")
      (node (ref "LED3") (pin "2") (pinfunction "2_2") (pintype "passive"))
      (node (ref "R1") (pin "2") (pinfunction "2_2") (pintype "passive"))
    )
    (net (code "66") (name "Net-(Q1-D)") (class "Default")
      (node (ref "Q1") (pin "3") (pinfunction "D_3") (pintype "passive"))
      (node (ref "R1") (pin "1") (pinfunction "1_1") (pintype "passive"))
    )
    (net (code "67") (name "Net-(Q1-G)") (class "Default")
      (node (ref "Q1") (pin "1") (pinfunction "G_1") (pintype "passive"))
      (node (ref "R2") (pin "2") (pinfunction "2_2") (pintype "passive"))
      (node (ref "RN1") (pin "4") (pinfunction "1_4") (pintype "passive"))
    )
    (net (code "68") (name "Net-(U1-PH0{slash}OSC_IN)") (class "Default")
      (node (ref "C41") (pin "2") (pinfunction "2_2") (pintype "passive"))
      (node (ref "U1") (pin "12") (pinfunction "PH0/OSC_IN_12") (pintype "bidirectional"))
      (node (ref "Y1") (pin "1") (pinfunction "1_1") (pintype "passive"))
    )
    (net (code "69") (name "Net-(U1-PH1{slash}OSC_OUT)") (class "Default")
      (node (ref "C40") (pin "2") (pinfunction "2_2") (pintype "passive"))
      (node (ref "U1") (pin "13") (pinfunction "PH1/OSC_OUT_13") (pintype "bidirectional"))
      (node (ref "Y1") (pin "3") (pinfunction "2_3") (pintype "passive"))
    )
    (net (code "70") (name "Net-(U1-VDDA)") (class "Default")
      (node (ref "C4") (pin "1") (pinfunction "1_1") (pintype "passive"))
      (node (ref "C5") (pin "1") (pinfunction "1_1") (pintype "passive"))
      (node (ref "L1") (pin "1") (pinfunction "1_1") (pintype "passive"))
      (node (ref "U1") (pin "20") (pinfunction "VREF_20") (pintype "power_in"))
      (node (ref "U1") (pin "21") (pinfunction "VDDA_21") (pintype "power_in"))
    )
    (net (code "71") (name "Net-(U2-DVDD)") (class "Default")
      (node (ref "C19") (pin "1") (pinfunction "1_1") (pintype "passive"))
      (node (ref "U2") (pin "E3") (pinfunction "DVDD_E3") (pintype "power_in"))
    )
    (net (code "72") (name "Net-(U2-VREFH)") (class "Default")
      (node (ref "C20") (pin "1") (pinfunction "1_1") (pintype "passive"))
      (node (ref "U2") (pin "A3") (pinfunction "VREFH_A3") (pintype "power_in"))
    )
    (net (code "73") (name "Net-(U2-VREFN)") (class "Default")
      (node (ref "C21") (pin "1") (pinfunction "1_1") (pintype "passive"))
      (node (ref "U2") (pin "B2") (pinfunction "VREFN_B2") (pintype "power_in"))
    )
    (net (code "74") (name "Net-(U5-NR)") (class "Default")
      (node (ref "C7") (pin "1") (pinfunction "1_1") (pintype "passive"))
      (node (ref "U5") (pin "4") (pinfunction "NR_4") (pintype "passive"))
    )
    (net (code "75") (name "Net-(U8-VOUT{slash}FB)") (class "Default")
      (node (ref "R10") (pin "1") (pinfunction "1_1") (pintype "passive"))
      (node (ref "R5") (pin "2") (pinfunction "2_2") (pintype "passive"))
      (node (ref "U8") (pin "4") (pinfunction "VOUT/FB_4") (pintype "passive"))
    )
    (net (code "76") (name "Net-(X1-5V)") (class "Default")
      (node (ref "L2") (pin "1") (pinfunction "1_1") (pintype "passive"))
      (node (ref "X1") (pin "1") (pinfunction "5V_1") (pintype "power_in"))
    )
    (net (code "77") (name "RAW") (class "Default")
      (node (ref "C44") (pin "2") (pinfunction "2_2") (pintype "passive"))
      (node (ref "D3") (pin "1") (pinfunction "C_1") (pintype "passive"))
      (node (ref "Q2") (pin "2") (pinfunction "S_2") (pintype "passive"))
      (node (ref "U8") (pin "1") (pinfunction "VIN_1") (pintype "power_in"))
      (node (ref "U8") (pin "3") (pinfunction "EN_3") (pintype "passive"))
    )
    (net (code "78") (name "VBUS") (class "Default")
      (node (ref "L2") (pin "2") (pinfunction "2_2") (pintype "passive"))
      (node (ref "Q2") (pin "3") (pinfunction "D_3") (pintype "passive"))
      (node (ref "U1") (pin "68") (pinfunction "PA9/USART1_TX/TIM1_CH2/I2C3_SMBA/DCMI_D0/OTG_FS_VBUS_68") (pintype "bidirectional"))
    )
    (net (code "79") (name "VCC") (class "Default")
      (node (ref "C10") (pin "1") (pinfunction "1_1") (pintype "passive"))
      (node (ref "C11") (pin "A") (pinfunction "+_A") (pintype "passive"))
      (node (ref "C13") (pin "1") (pinfunction "1_1") (pintype "passive"))
      (node (ref "C14") (pin "A") (pinfunction "+_A") (pintype "passive"))
      (node (ref "C16") (pin "1") (pinfunction "1_1") (pintype "passive"))
      (node (ref "C17") (pin "1") (pinfunction "1_1") (pintype "passive"))
      (node (ref "C2") (pin "2") (pinfunction "2_2") (pintype "passive"))
      (node (ref "C3") (pin "2") (pinfunction "2_2") (pintype "passive"))
      (node (ref "C6") (pin "1") (pinfunction "1_1") (pintype "passive"))
      (node (ref "C8") (pin "1") (pinfunction "1_1") (pintype "passive"))
      (node (ref "C9") (pin "1") (pinfunction "1_1") (pintype "passive"))
      (node (ref "JP1") (pin "8") (pinfunction "8_8") (pintype "passive"))
      (node (ref "JP3") (pin "5") (pinfunction "5_5") (pintype "passive"))
      (node (ref "L1") (pin "2") (pinfunction "2_2") (pintype "passive"))
      (node (ref "L3") (pin "2") (pinfunction "2_2") (pintype "passive"))
      (node (ref "LED1") (pin "2") (pinfunction "COM_2") (pintype "bidirectional"))
      (node (ref "LED2") (pin "1") (pinfunction "1_1") (pintype "passive"))
      (node (ref "R10") (pin "2") (pinfunction "2_2") (pintype "passive"))
      (node (ref "R4") (pin "1") (pinfunction "1_1") (pintype "passive"))
      (node (ref "R6") (pin "1") (pinfunction "1_1") (pintype "passive"))
      (node (ref "RN2") (pin "5") (pinfunction "2_5") (pintype "passive"))
      (node (ref "RN2") (pin "6") (pinfunction "2_6") (pintype "passive"))
      (node (ref "RN2") (pin "7") (pinfunction "2_7") (pintype "passive"))
      (node (ref "RN2") (pin "8") (pinfunction "2_8") (pintype "passive"))
      (node (ref "RN3") (pin "1") (pinfunction "1_1") (pintype "passive"))
      (node (ref "RN3") (pin "2") (pinfunction "1_2") (pintype "passive"))
      (node (ref "RN3") (pin "5") (pinfunction "2_5") (pintype "passive"))
      (node (ref "TF1") (pin "4") (pinfunction "VDD_4") (pintype "passive"))
      (node (ref "U1") (pin "100") (pinfunction "VDD_100") (pintype "power_in"))
      (node (ref "U1") (pin "11") (pinfunction "VDD_11") (pintype "power_in"))
      (node (ref "U1") (pin "27") (pinfunction "VDD_27") (pintype "power_in"))
      (node (ref "U1") (pin "50") (pinfunction "VDD_50") (pintype "power_in"))
      (node (ref "U1") (pin "6") (pinfunction "VBAT_6") (pintype "power_in"))
      (node (ref "U1") (pin "75") (pinfunction "VDD_75") (pintype "power_in"))
      (node (ref "U2") (pin "E5") (pinfunction "DOVDD_E5") (pintype "power_in"))
      (node (ref "U5") (pin "1") (pinfunction "IN_1") (pintype "input"))
      (node (ref "U5") (pin "3") (pinfunction "EN_3") (pintype "input"))
    )
    (net (code "80") (name "VDDA") (class "Default")
      (node (ref "C12") (pin "2") (pinfunction "2_2") (pintype "passive"))
      (node (ref "R3") (pin "2") (pinfunction "2_2") (pintype "passive"))
      (node (ref "U5") (pin "5") (pinfunction "OUT_5") (pintype "output"))
    )
    (net (code "81") (name "VIN") (class "Default")
      (node (ref "D3") (pin "2") (pinfunction "A_2") (pintype "passive"))
      (node (ref "JP2") (pin "7") (pinfunction "7_7") (pintype "passive"))
      (node (ref "Q2") (pin "1") (pinfunction "G_1") (pintype "passive"))
      (node (ref "R9") (pin "2") (pinfunction "2_2") (pintype "passive"))
      (node (ref "X4") (pin "1") (pinfunction "2_1") (pintype "passive"))
    )
    (net (code "82") (name "unconnected-(LM1-Pad1)") (class "Default")
      (node (ref "LM1") (pin "1") (pinfunction "1_1") (pintype "power_in"))
    )
    (net (code "83") (name "unconnected-(LM1-Pad2)") (class "Default")
      (node (ref "LM1") (pin "2") (pinfunction "2_2") (pintype "power_in"))
    )
    (net (code "84") (name "unconnected-(TF1-Pad10)") (class "Default")
      (node (ref "TF1") (pin "10") (pintype "passive"))
    )
    (net (code "85") (name "unconnected-(U1-PA0{slash}USART2_CTS{slash}UART4_TX{slash}TIM2_CH1_ETR{slash}WKUP{slash}TIM5_CH1{slash}TIM8_ETR-Pad22)") (class "Default")
      (node (ref "U1") (pin "22") (pinfunction "PA0/USART2_CTS/UART4_TX/TIM2_CH1_ETR/WKUP/TIM5_CH1/TIM8_ETR_22") (pintype "bidirectional+no_connect"))
    )
    (net (code "86") (name "unconnected-(U1-PA1{slash}USART2_RTS{slash}UART4_RX{slash}TIM5_CH2{slash}TIMM2_CH2{slash}EVENTOUT-Pad23)") (class "Default")
      (node (ref "U1") (pin "23") (pinfunction "PA1/USART2_RTS/UART4_RX/TIM5_CH2/TIMM2_CH2/EVENTOUT_23") (pintype "bidirectional+no_connect"))
    )
    (net (code "87") (name "unconnected-(U1-PA2{slash}USART2_TX{slash}TIM5_CH3{slash}TIM9_CH1{slash}TIM2_CH3{slash}ETH_MDIO-Pad24)") (class "Default")
      (node (ref "U1") (pin "24") (pinfunction "PA2/USART2_TX/TIM5_CH3/TIM9_CH1/TIM2_CH3/ETH_MDIO_24") (pintype "bidirectional+no_connect"))
    )
    (net (code "88") (name "unconnected-(U1-PA3{slash}USART2_RX{slash}TIM5_CH4{slash}TIM9_CH2{slash}TIM2_CH4{slash}OTG_HS_ULPI_D0-Pad25)") (class "Default")
      (node (ref "U1") (pin "25") (pinfunction "PA3/USART2_RX/TIM5_CH4/TIM9_CH2/TIM2_CH4/OTG_HS_ULPI_D0_25") (pintype "bidirectional+no_connect"))
    )
    (net (code "89") (name "unconnected-(U1-PA7{slash}SPI1_MOSI{slash}TIM8_CH1N{slash}TIM14_CH1TIM3_CH2-Pad31)") (class "Default")
      (node (ref "U1") (pin "31") (pinfunction "PA7/SPI1_MOSI/TIM8_CH1N/TIM14_CH1TIM3_CH2_31") (pintype "bidirectional+no_connect"))
    )
    (net (code "90") (name "unconnected-(U1-PB0{slash}TIM3_CH3{slash}TIM8_CH2N{slash}OTG_HS_ULPI_D1{slash}ETH_MII_RXD2{slash}TIM1_CH2N{slash}-Pad34)") (class "Default")
      (node (ref "U1") (pin "34") (pinfunction "PB0/TIM3_CH3/TIM8_CH2N/OTG_HS_ULPI_D1/ETH_MII_RXD2/TIM1_CH2N/_34") (pintype "bidirectional+no_connect"))
    )
    (net (code "91") (name "unconnected-(U1-PB1{slash}TIM3_CH4{slash}TIM8_CH3N{slash}OTG_HS_ULPI_D2{slash}ETH_MII_RXD3{slash}OTG_HS_INTN{slash}-Pad35)") (class "Default")
      (node (ref "U1") (pin "35") (pinfunction "PB1/TIM3_CH4/TIM8_CH3N/OTG_HS_ULPI_D2/ETH_MII_RXD3/OTG_HS_INTN/_35") (pintype "bidirectional+no_connect"))
    )
    (net (code "92") (name "unconnected-(U1-PB2{slash}SAI1_SD_A{slash}SPI3_MOSI{slash}I2S3_SD{slash}QUADSPI_CLK{slash}EVENTOUT-Pad36)") (class "Default")
      (node (ref "U1") (pin "36") (pinfunction "PB2/SAI1_SD_A/SPI3_MOSI/I2S3_SD/QUADSPI_CLK/EVENTOUT_36") (pintype "bidirectional+no_connect"))
    )
    (net (code "93") (name "unconnected-(U1-PC3{slash}SPI2_MOSI{slash}I2S2_SD{slash}OTG_HS_ULPI_NXT{slash}ETH_MII_TX_CLK{slash}ADC123_IN13-Pad18)") (class "Default")
      (node (ref "U1") (pin "18") (pinfunction "PC3/SPI2_MOSI/I2S2_SD/OTG_HS_ULPI_NXT/ETH_MII_TX_CLK/ADC123_IN13_18") (pintype "bidirectional+no_connect"))
    )
    (net (code "94") (name "unconnected-(U1-PC4{slash}ETH_RMII_RX_D0{slash}ETH_MII_RX_D0{slash}ADC12_IN14-Pad32)") (class "Default")
      (node (ref "U1") (pin "32") (pinfunction "PC4/ETH_RMII_RX_D0/ETH_MII_RX_D0/ADC12_IN14_32") (pintype "bidirectional+no_connect"))
    )
    (net (code "95") (name "unconnected-(U1-PC5{slash}ETH_RMII_RX_D1{slash}ETH_MII_RX_D1{slash}ADC12_IN15-Pad33)") (class "Default")
      (node (ref "U1") (pin "33") (pinfunction "PC5/ETH_RMII_RX_D1/ETH_MII_RX_D1/ADC12_IN15_33") (pintype "bidirectional+no_connect"))
    )
    (net (code "96") (name "unconnected-(U1-PC13{slash}RTC_AF1-Pad7)") (class "Default")
      (node (ref "U1") (pin "7") (pinfunction "PC13/RTC_AF1_7") (pintype "bidirectional+no_connect"))
    )
    (net (code "97") (name "unconnected-(U1-PC14{slash}OSC32_IN-Pad8)") (class "Default")
      (node (ref "U1") (pin "8") (pinfunction "PC14/OSC32_IN_8") (pintype "bidirectional+no_connect"))
    )
    (net (code "98") (name "unconnected-(U1-PC15{slash}OSC32_OUT-Pad9)") (class "Default")
      (node (ref "U1") (pin "9") (pinfunction "PC15/OSC32_OUT_9") (pintype "bidirectional+no_connect"))
    )
    (net (code "99") (name "unconnected-(U1-PD10{slash}FSMC_D15{slash}USART3_CK-Pad57)") (class "Default")
      (node (ref "U1") (pin "57") (pinfunction "PD10/FSMC_D15/USART3_CK_57") (pintype "bidirectional+no_connect"))
    )
    (net (code "100") (name "unconnected-(U1-PD11{slash}FSMC_A16{slash}USART3_CTS-Pad58)") (class "Default")
      (node (ref "U1") (pin "58") (pinfunction "PD11/FSMC_A16/USART3_CTS_58") (pintype "bidirectional+no_connect"))
    )
    (net (code "101") (name "unconnected-(U1-PD15{slash}FSMC_D1{slash}TIM4_CH4-Pad62)") (class "Default")
      (node (ref "U1") (pin "62") (pinfunction "PD15/FSMC_D1/TIM4_CH4_62") (pintype "bidirectional+no_connect"))
    )
    (net (code "102") (name "unconnected-(U1-PE3{slash}TRACED0{slash}FSMC_A19-Pad2)") (class "Default")
      (node (ref "U1") (pin "2") (pinfunction "PE3/TRACED0/FSMC_A19_2") (pintype "bidirectional+no_connect"))
    )
    (net (code "103") (name "unconnected-(U1-PE7{slash}FSMC_D4{slash}TIM1_ETR-Pad37)") (class "Default")
      (node (ref "U1") (pin "37") (pinfunction "PE7/FSMC_D4/TIM1_ETR_37") (pintype "bidirectional+no_connect"))
    )
    (net (code "104") (name "unconnected-(U1-PE8{slash}FSMC_D5{slash}TIM1_CH1N-Pad38)") (class "Default")
      (node (ref "U1") (pin "38") (pinfunction "PE8/FSMC_D5/TIM1_CH1N_38") (pintype "bidirectional+no_connect"))
    )
    (net (code "105") (name "unconnected-(U1-PE9{slash}FSMC_D6{slash}TIM1_CH1-Pad39)") (class "Default")
      (node (ref "U1") (pin "39") (pinfunction "PE9/FSMC_D6/TIM1_CH1_39") (pintype "bidirectional+no_connect"))
    )
    (net (code "106") (name "unconnected-(U1-PE10{slash}FSMC_D7{slash}TIM1_CH2N-Pad40)") (class "Default")
      (node (ref "U1") (pin "40") (pinfunction "PE10/FSMC_D7/TIM1_CH2N_40") (pintype "bidirectional+no_connect"))
    )
    (net (code "107") (name "unconnected-(U1-PE11{slash}FSMC_D8{slash}TIM1_CH2-Pad41)") (class "Default")
      (node (ref "U1") (pin "41") (pinfunction "PE11/FSMC_D8/TIM1_CH2_41") (pintype "bidirectional+no_connect"))
    )
    (net (code "108") (name "unconnected-(U1-PE12{slash}FSMC_D9{slash}TIM1_CH3N-Pad42)") (class "Default")
      (node (ref "U1") (pin "42") (pinfunction "PE12/FSMC_D9/TIM1_CH3N_42") (pintype "bidirectional+no_connect"))
    )
    (net (code "109") (name "unconnected-(U1-PE13{slash}FSMC_D10{slash}TIM1_CH3-Pad43)") (class "Default")
      (node (ref "U1") (pin "43") (pinfunction "PE13/FSMC_D10/TIM1_CH3_43") (pintype "bidirectional+no_connect"))
    )
    (net (code "110") (name "unconnected-(U1-PE14{slash}FSMC_D11{slash}TIM1_CH4-Pad44)") (class "Default")
      (node (ref "U1") (pin "44") (pinfunction "PE14/FSMC_D11/TIM1_CH4_44") (pintype "bidirectional+no_connect"))
    )
    (net (code "111") (name "unconnected-(U1-PE15FSMC_D12{slash}TIM1_BKIN-Pad45)") (class "Default")
      (node (ref "U1") (pin "45") (pinfunction "PE15FSMC_D12/TIM1_BKIN_45") (pintype "bidirectional+no_connect"))
    )
    (net (code "112") (name "unconnected-(U2-D0-PadA6)") (class "Default")
      (node (ref "U2") (pin "A6") (pinfunction "D0_A6") (pintype "bidirectional"))
    )
    (net (code "113") (name "unconnected-(U2-D1-PadE2)") (class "Default")
      (node (ref "U2") (pin "E2") (pinfunction "D1_E2") (pintype "bidirectional"))
    )
    (net (code "114") (name "unconnected-(X1-ID-Pad4)") (class "Default")
      (node (ref "X1") (pin "4") (pinfunction "ID_4") (pintype "bidirectional+no_connect"))
    )
    (net (code "115") (name "unconnected-(X1-SLD-PadS1_S2_S3_S4_S5_S6)") (class "Default")
      (node (ref "X1") (pin "S1_S2_S3_S4_S5_S6") (pinfunction "SLD_S1_S2_S3_S4_S5_S6") (pintype "passive+no_connect"))
    )
  )
)
